# Main.net
KiCad netlist of a schematic drawn in Altium Designer
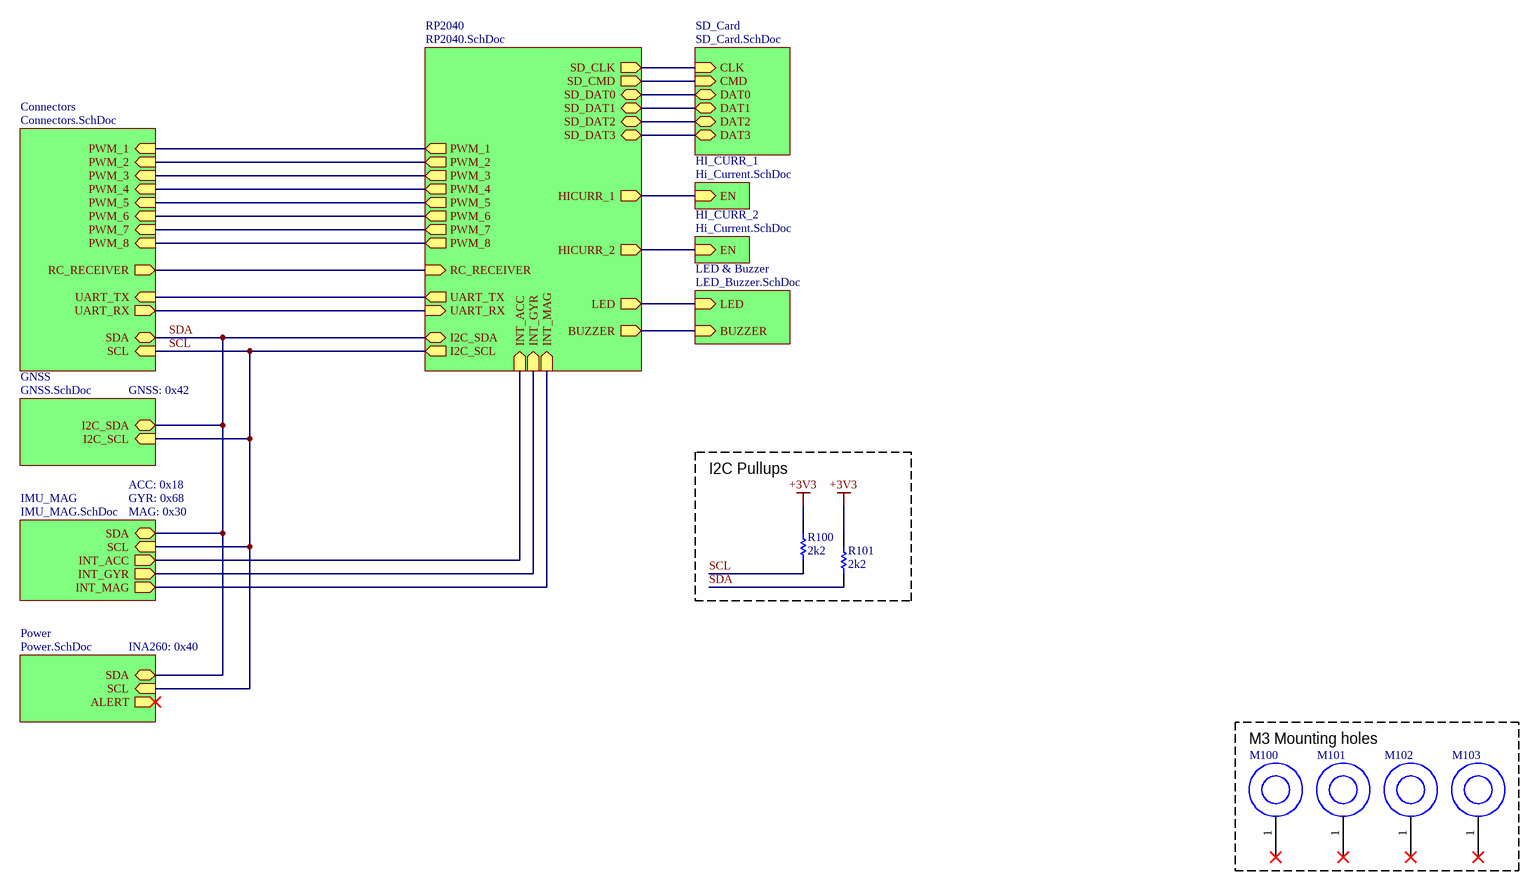
[diagram p0: Main.SchDoc]

(export (version "E")
  (design (tool "Eeschema 10.0.6"))
  (components
    (comp (ref "M100")
      (value "Mounting Screw")
      (footprint "M3_SCREW")
      (description "M4 and M3 scew holes, just pick the right footprint")
      (libsource (lib "Moonlight_Components") (part "Mounting Screw"))
    )
    (comp (ref "M101")
      (value "Mounting Screw")
      (footprint "M3_SCREW")
      (description "M4 and M3 scew holes, just pick the right footprint")
      (libsource (lib "Moonlight_Components") (part "Mounting Screw"))
    )
    (comp (ref "M102")
      (value "Mounting Screw")
      (footprint "M3_SCREW")
      (description "M4 and M3 scew holes, just pick the right footprint")
      (libsource (lib "Moonlight_Components") (part "Mounting Screw"))
    )
    (comp (ref "M103")
      (value "Mounting Screw")
      (footprint "M3_SCREW")
      (description "M4 and M3 scew holes, just pick the right footprint")
      (libsource (lib "Moonlight_Components") (part "Mounting Screw"))
    )
    (comp (ref "R100")
      (value "2k2")
      (footprint "0603_RES")
      (libsource (lib "Moonlight_Components") (part "Resistor"))
    )
    (comp (ref "R101")
      (value "2k2")
      (footprint "0603_RES")
      (libsource (lib "Moonlight_Components") (part "Resistor"))
    )
  )
  (nets
    (net (code "1") (name "+3V3") (class "Default")
      (node (ref "R100") (pin "1") (pinfunction "1_1") (pintype "passive"))
      (node (ref "R101") (pin "1") (pinfunction "1_1") (pintype "passive"))
    )
    (net (code "23") (name "/SCL") (class "Default")
      (node (ref "R100") (pin "2") (pinfunction "2_2") (pintype "passive"))
    )
    (net (code "24") (name "/SDA") (class "Default")
      (node (ref "R101") (pin "2") (pinfunction "2_2") (pintype "passive"))
    )
    (net (code "29") (name "unconnected-(M100-19-Pad1)") (class "Default")
      (node (ref "M100") (pin "1") (pinfunction "19_1") (pintype "passive+no_connect"))
    )
    (net (code "30") (name "unconnected-(M101-19-Pad1)") (class "Default")
      (node (ref "M101") (pin "1") (pinfunction "19_1") (pintype "passive+no_connect"))
    )
    (net (code "31") (name "unconnected-(M102-19-Pad1)") (class "Default")
      (node (ref "M102") (pin "1") (pinfunction "19_1") (pintype "passive+no_connect"))
    )
    (net (code "32") (name "unconnected-(M103-19-Pad1)") (class "Default")
      (node (ref "M103") (pin "1") (pinfunction "19_1") (pintype "passive+no_connect"))
    )
  )
)
